# circuit_on_off.net
KiCad netlist of a schematic drawn in Altium Designer
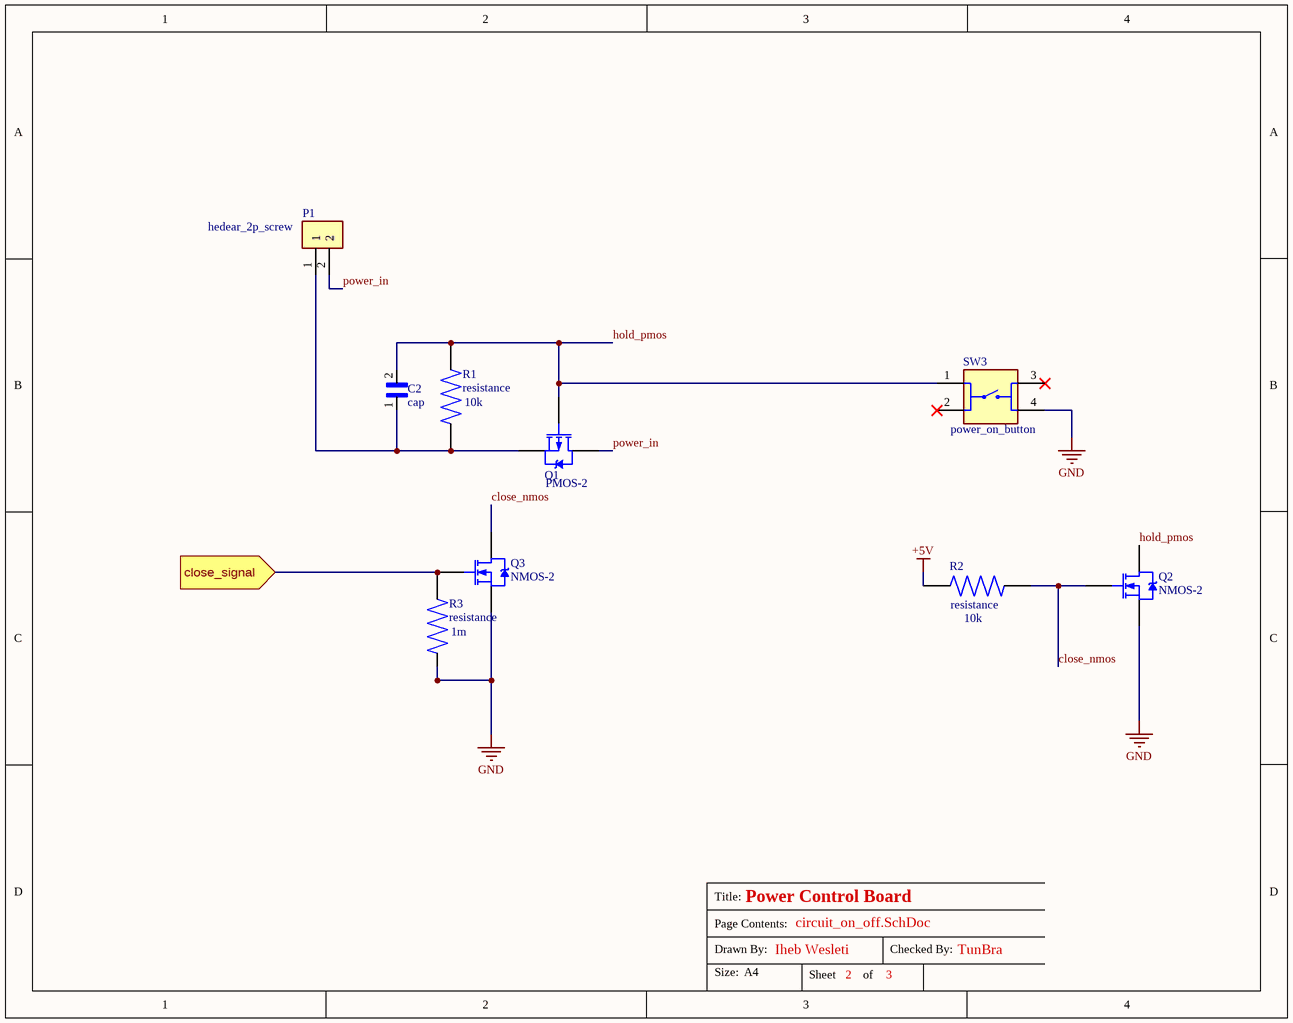
[diagram p0: circuit_on_off.SchDoc]

(export (version "E")
  (design (tool "Eeschema 10.0.6"))
  (components
    (comp (ref "C2")
      (value "cap")
      (footprint "cap")
      (description "Lead Capacitor X7R_EIA_ with Capacitance: 0.10F and Rated Voltage: 1000Vdc")
      (fields (field (name "MF") "Murata") (field (name "MP") "RDER73A104K5E1H03A"))
      (libsource (lib "Schlib_circuit_de_puissance") (part "cap"))
    )
    (comp (ref "P1")
      (value "hedear_2p_screw")
      (footprint "hedear_2p_screw")
      (fields (field (name "MF") "TE Connectivity") (field (name "MP") "282837-2"))
      (libsource (lib "Schlib_circuit_de_puissance") (part "hedear_2p_screw"))
    )
    (comp (ref "Q1")
      (value "PMOS-2")
      (footprint "TO-220AB")
      (description "P-Channel Power MOSFET")
      (fields (field (name "PUBLISHER") "Altium Limited"))
      (libsource (lib "Miscellaneous Devices") (part "PMOS-2"))
    )
    (comp (ref "Q2")
      (value "NMOS-2")
      (footprint "TO-220AB")
      (description "N-Channel Power MOSFET")
      (fields (field (name "PUBLISHER") "Altium Limited"))
      (libsource (lib "Miscellaneous Devices") (part "NMOS-2"))
    )
    (comp (ref "Q3")
      (value "NMOS-2")
      (footprint "TO-220AB")
      (description "N-Channel Power MOSFET")
      (fields (field (name "PUBLISHER") "Altium Limited"))
      (libsource (lib "Miscellaneous Devices") (part "NMOS-2"))
    )
    (comp (ref "R1")
      (value "resistance")
      (footprint "resistance")
      (fields
        (field (name "MP") "CBT50J5R1")
        (field (name "ALTIUM_VALUE") "10k")
        (field (name "MF") "TE Connectivity / AMP")
      )
      (libsource (lib "Schlib_circuit_de_puissance") (part "resistance"))
    )
    (comp (ref "R2")
      (value "resistance")
      (footprint "resistance")
      (fields
        (field (name "MP") "CBT50J5R1")
        (field (name "ALTIUM_VALUE") "10k")
        (field (name "MF") "TE Connectivity / AMP")
      )
      (libsource (lib "Schlib_circuit_de_puissance") (part "resistance"))
    )
    (comp (ref "R3")
      (value "resistance")
      (footprint "resistance")
      (fields
        (field (name "MP") "CBT50J5R1")
        (field (name "ALTIUM_VALUE") "1m")
        (field (name "MF") "TE Connectivity / AMP")
      )
      (libsource (lib "Schlib_circuit_de_puissance") (part "resistance"))
    )
    (comp (ref "SW3")
      (value "power_on_button")
      (footprint "push_button_pcb")
      (description "Switch Push Button OFF (ON) SPST Round Button 0.05A 24VDC Momentary Contact PC Pins Thru-Hole")
      (fields (field (name "MP") "1825910-6") (field (name "MF") "TE Connectivity"))
      (libsource (lib "Schlib_circuit_de_puissance") (part "push_button"))
    )
  )
  (nets
    (net (code "1") (name "+5V") (class "Default")
      (node (ref "R2") (pin "2") (pinfunction "2_2") (pintype "passive"))
    )
    (net (code "2") (name "/close_nmos") (class "Default")
      (node (ref "Q2") (pin "1") (pinfunction "G_1") (pintype "passive"))
      (node (ref "Q3") (pin "2") (pinfunction "D_2") (pintype "passive"))
      (node (ref "R2") (pin "1") (pinfunction "1_1") (pintype "passive"))
    )
    (net (code "3") (name "/close_signal") (class "Default")
      (node (ref "Q3") (pin "1") (pinfunction "G_1") (pintype "passive"))
      (node (ref "R3") (pin "1") (pinfunction "1_1") (pintype "passive"))
    )
    (net (code "4") (name "/hold_pmos") (class "Default")
      (node (ref "C2") (pin "2") (pinfunction "2_2") (pintype "passive"))
      (node (ref "Q1") (pin "1") (pinfunction "G_1") (pintype "passive"))
      (node (ref "Q2") (pin "2") (pinfunction "D_2") (pintype "passive"))
      (node (ref "R1") (pin "2") (pinfunction "2_2") (pintype "passive"))
      (node (ref "SW3") (pin "1") (pinfunction "1_1") (pintype "passive"))
    )
    (net (code "5") (name "/power_in") (class "Default")
      (node (ref "P1") (pin "2") (pinfunction "2_2") (pintype "passive"))
      (node (ref "Q1") (pin "2") (pinfunction "D_2") (pintype "passive"))
    )
    (net (code "6") (name "GND") (class "Default")
      (node (ref "Q2") (pin "3") (pinfunction "S_3") (pintype "passive"))
      (node (ref "Q3") (pin "3") (pinfunction "S_3") (pintype "passive"))
      (node (ref "R3") (pin "2") (pinfunction "2_2") (pintype "passive"))
      (node (ref "SW3") (pin "4") (pinfunction "4_4") (pintype "passive"))
    )
    (net (code "7") (name "Net-(Q1-S)") (class "Default")
      (node (ref "C2") (pin "1") (pinfunction "1_1") (pintype "passive"))
      (node (ref "P1") (pin "1") (pinfunction "1_1") (pintype "passive"))
      (node (ref "Q1") (pin "3") (pinfunction "S_3") (pintype "passive"))
      (node (ref "R1") (pin "1") (pinfunction "1_1") (pintype "passive"))
    )
    (net (code "8") (name "unconnected-(SW3-Pad2)") (class "Default")
      (node (ref "SW3") (pin "2") (pinfunction "2_2") (pintype "passive+no_connect"))
    )
    (net (code "9") (name "unconnected-(SW3-Pad3)") (class "Default")
      (node (ref "SW3") (pin "3") (pinfunction "3_3") (pintype "passive+no_connect"))
    )
  )
)
